# 4channelsRelay.net
KiCad netlist of a schematic drawn in EAGLE
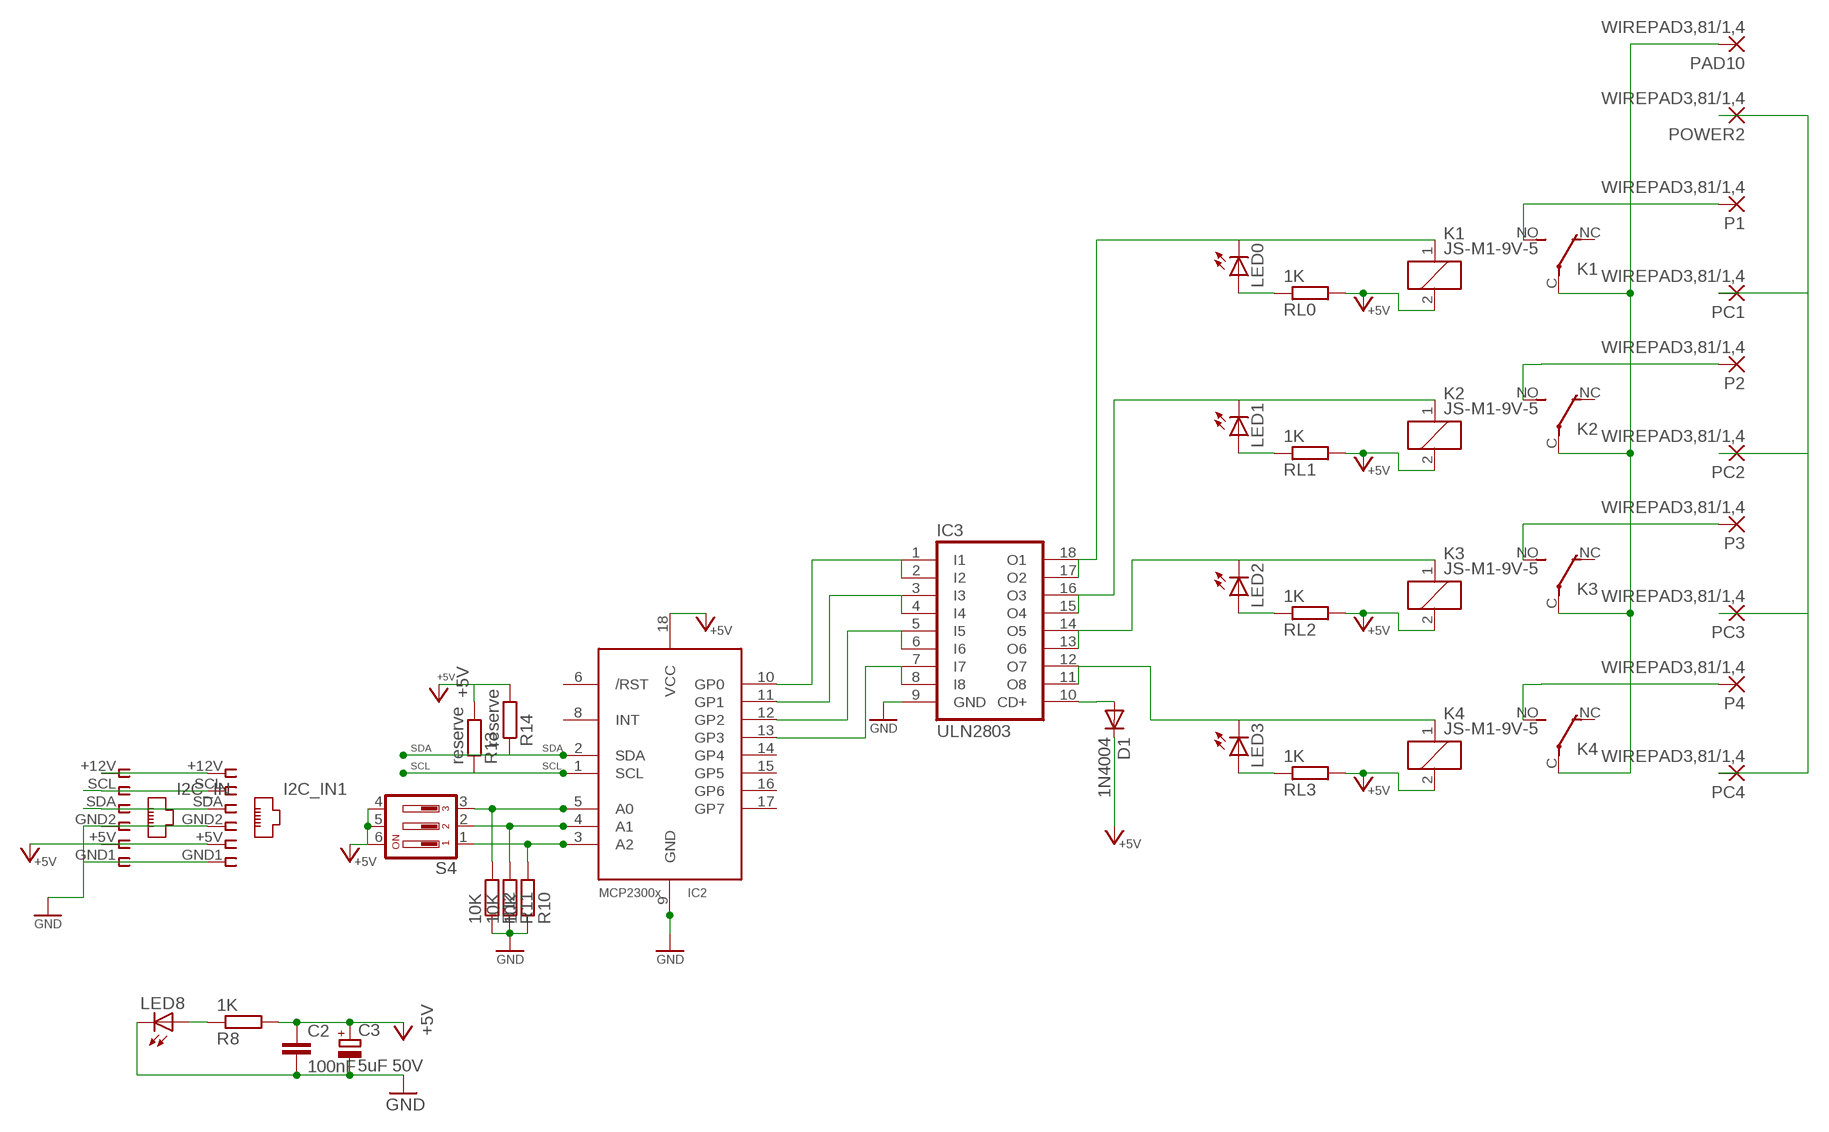
[diagram p0: schematic, sheet 1]

(export (version "E")
  (design (tool "Eeschema 10.0.6"))
  (components
    (comp (ref "C2")
      (value "100nF")
      (footprint "eagle-import:C1206")
      (libsource (lib "eagle-import") (part "C-EUC1206"))
    )
    (comp (ref "C3")
      (value "5uF 50V")
      (footprint "eagle-import:E3,5-8")
      (libsource (lib "eagle-import") (part "CPOL-EUE3.5-8"))
    )
    (comp (ref "D1")
      (value "1N4004")
      (footprint "eagle-import:DO41-10")
      (libsource (lib "eagle-import") (part "1N4004"))
    )
    (comp (ref "I2C_IN")
      (value "I2C 1")
      (footprint "eagle-import:RJ12-STRAIGHT-I2C")
      (libsource (lib "eagle-import") (part "RJ12STRAIGHT-I2C"))
    )
    (comp (ref "I2C_IN1")
      (value "I2C 2")
      (footprint "eagle-import:RJ12-STRAIGHT-I2C")
      (libsource (lib "eagle-import") (part "RJ12STRAIGHT-I2C"))
    )
    (comp (ref "IC2")
      (value "MCP2300X/P")
      (footprint "eagle-import:DIL18")
      (libsource (lib "eagle-import") (part "MCP2300X/P"))
    )
    (comp (ref "IC3")
      (value "ULN2803")
      (footprint "eagle-import:DIL18")
      (libsource (lib "eagle-import") (part "ULN2803A"))
    )
    (comp (ref "K1")
      (value "JS-M1-9V-5")
      (footprint "eagle-import:JS-M")
      (libsource (lib "eagle-import") (part "JS-M1-9V-5"))
    )
    (comp (ref "K2")
      (value "JS-M1-9V-5")
      (footprint "eagle-import:JS-M")
      (libsource (lib "eagle-import") (part "JS-M1-9V-5"))
    )
    (comp (ref "K3")
      (value "JS-M1-9V-5")
      (footprint "eagle-import:JS-M")
      (libsource (lib "eagle-import") (part "JS-M1-9V-5"))
    )
    (comp (ref "K4")
      (value "JS-M1-9V-5")
      (footprint "eagle-import:JS-M")
      (libsource (lib "eagle-import") (part "JS-M1-9V-5"))
    )
    (comp (ref "LED0")
      (value "LED3MM")
      (footprint "eagle-import:LED3MM")
      (libsource (lib "eagle-import") (part "LED3MM"))
    )
    (comp (ref "LED1")
      (value "LED3MM")
      (footprint "eagle-import:LED3MM")
      (libsource (lib "eagle-import") (part "LED3MM"))
    )
    (comp (ref "LED2")
      (value "LED3MM")
      (footprint "eagle-import:LED3MM")
      (libsource (lib "eagle-import") (part "LED3MM"))
    )
    (comp (ref "LED3")
      (value "LED3MM")
      (footprint "eagle-import:LED3MM")
      (libsource (lib "eagle-import") (part "LED3MM"))
    )
    (comp (ref "LED8")
      (value "LED3MM")
      (footprint "eagle-import:LED3MM")
      (libsource (lib "eagle-import") (part "LED3MM"))
    )
    (comp (ref "P1")
      (value "WIREPAD3,81/1,4")
      (footprint "eagle-import:3,81_1,4")
      (libsource (lib "eagle-import") (part "WIREPAD3,81/1,4"))
    )
    (comp (ref "P2")
      (value "WIREPAD3,81/1,4")
      (footprint "eagle-import:3,81_1,4")
      (libsource (lib "eagle-import") (part "WIREPAD3,81/1,4"))
    )
    (comp (ref "P3")
      (value "WIREPAD3,81/1,4")
      (footprint "eagle-import:3,81_1,4")
      (libsource (lib "eagle-import") (part "WIREPAD3,81/1,4"))
    )
    (comp (ref "P4")
      (value "WIREPAD3,81/1,4")
      (footprint "eagle-import:3,81_1,4")
      (libsource (lib "eagle-import") (part "WIREPAD3,81/1,4"))
    )
    (comp (ref "PAD10")
      (value "WIREPAD3,81/1,4")
      (footprint "eagle-import:3,81_1,4")
      (libsource (lib "eagle-import") (part "WIREPAD3,81/1,4"))
    )
    (comp (ref "PC1")
      (value "WIREPAD3,81/1,4")
      (footprint "eagle-import:3,81_1,4")
      (libsource (lib "eagle-import") (part "WIREPAD3,81/1,4"))
    )
    (comp (ref "PC2")
      (value "WIREPAD3,81/1,4")
      (footprint "eagle-import:3,81_1,4")
      (libsource (lib "eagle-import") (part "WIREPAD3,81/1,4"))
    )
    (comp (ref "PC3")
      (value "WIREPAD3,81/1,4")
      (footprint "eagle-import:3,81_1,4")
      (libsource (lib "eagle-import") (part "WIREPAD3,81/1,4"))
    )
    (comp (ref "PC4")
      (value "WIREPAD3,81/1,4")
      (footprint "eagle-import:3,81_1,4")
      (libsource (lib "eagle-import") (part "WIREPAD3,81/1,4"))
    )
    (comp (ref "POWER2")
      (value "WIREPAD3,81/1,4")
      (footprint "eagle-import:3,81_1,4")
      (libsource (lib "eagle-import") (part "WIREPAD3,81/1,4"))
    )
    (comp (ref "R8")
      (value "1K")
      (footprint "eagle-import:M1206")
      (libsource (lib "eagle-import") (part "R-EU_M1206"))
    )
    (comp (ref "R10")
      (value "10K")
      (footprint "eagle-import:M1206")
      (libsource (lib "eagle-import") (part "R-EU_M1206"))
    )
    (comp (ref "R11")
      (value "10K")
      (footprint "eagle-import:M1206")
      (libsource (lib "eagle-import") (part "R-EU_M1206"))
    )
    (comp (ref "R12")
      (value "10K")
      (footprint "eagle-import:M1206")
      (libsource (lib "eagle-import") (part "R-EU_M1206"))
    )
    (comp (ref "R13")
      (value "reserve")
      (footprint "eagle-import:M1206")
      (libsource (lib "eagle-import") (part "R-EU_M1206"))
    )
    (comp (ref "R14")
      (value "reserve")
      (footprint "eagle-import:M1206")
      (libsource (lib "eagle-import") (part "R-EU_M1206"))
    )
    (comp (ref "RL0")
      (value "1K")
      (footprint "eagle-import:M1206")
      (libsource (lib "eagle-import") (part "R-EU_M1206"))
    )
    (comp (ref "RL1")
      (value "1K")
      (footprint "eagle-import:M1206")
      (libsource (lib "eagle-import") (part "R-EU_M1206"))
    )
    (comp (ref "RL2")
      (value "1K")
      (footprint "eagle-import:M1206")
      (libsource (lib "eagle-import") (part "R-EU_M1206"))
    )
    (comp (ref "RL3")
      (value "1K")
      (footprint "eagle-import:M1206")
      (libsource (lib "eagle-import") (part "R-EU_M1206"))
    )
    (comp (ref "S4")
      (value "DIP03YL")
      (footprint "eagle-import:DIP03YL")
      (libsource (lib "eagle-import") (part "DIP03YL"))
    )
  )
  (nets
    (net (code "1") (name "+5V") (class "Default")
      (node (ref "C2") (pin "1") (pinfunction "1_1") (pintype "passive"))
      (node (ref "C3") (pin "+") (pinfunction "+_+") (pintype "passive"))
      (node (ref "D1") (pin "C") (pinfunction "C_C") (pintype "passive"))
      (node (ref "I2C_IN") (pin "+5V") (pinfunction "5_+5V") (pintype "power_in"))
      (node (ref "I2C_IN1") (pin "+5V") (pinfunction "5_+5V") (pintype "power_in"))
      (node (ref "IC2") (pin "18") (pinfunction "VCC_18") (pintype "power_in"))
      (node (ref "K1") (pin "2") (pinfunction "2_2") (pintype "passive"))
      (node (ref "K2") (pin "2") (pinfunction "2_2") (pintype "passive"))
      (node (ref "K3") (pin "2") (pinfunction "2_2") (pintype "passive"))
      (node (ref "K4") (pin "2") (pinfunction "2_2") (pintype "passive"))
      (node (ref "R13") (pin "2") (pinfunction "2_2") (pintype "passive"))
      (node (ref "R14") (pin "2") (pinfunction "2_2") (pintype "passive"))
      (node (ref "R8") (pin "2") (pinfunction "2_2") (pintype "passive"))
      (node (ref "RL0") (pin "2") (pinfunction "2_2") (pintype "passive"))
      (node (ref "RL1") (pin "2") (pinfunction "2_2") (pintype "passive"))
      (node (ref "RL2") (pin "2") (pinfunction "2_2") (pintype "passive"))
      (node (ref "RL3") (pin "2") (pinfunction "2_2") (pintype "passive"))
      (node (ref "S4") (pin "4") (pinfunction "4_4") (pintype "passive"))
      (node (ref "S4") (pin "5") (pinfunction "5_5") (pintype "passive"))
      (node (ref "S4") (pin "6") (pinfunction "6_6") (pintype "passive"))
    )
    (net (code "2") (name "/SCL") (class "Default")
      (node (ref "I2C_IN") (pin "SCL") (pinfunction "2_SCL") (pintype "bidirectional"))
      (node (ref "I2C_IN1") (pin "SCL") (pinfunction "2_SCL") (pintype "bidirectional"))
      (node (ref "IC2") (pin "1") (pinfunction "SCL_1") (pintype "bidirectional"))
      (node (ref "R13") (pin "1") (pinfunction "1_1") (pintype "passive"))
    )
    (net (code "3") (name "/SDA") (class "Default")
      (node (ref "I2C_IN") (pin "SDA") (pinfunction "3_SDA") (pintype "bidirectional"))
      (node (ref "I2C_IN1") (pin "SDA") (pinfunction "3_SDA") (pintype "bidirectional"))
      (node (ref "IC2") (pin "2") (pinfunction "SDA_2") (pintype "bidirectional"))
      (node (ref "R14") (pin "1") (pinfunction "1_1") (pintype "passive"))
    )
    (net (code "4") (name "GND") (class "Default")
      (node (ref "C2") (pin "2") (pinfunction "2_2") (pintype "passive"))
      (node (ref "C3") (pin "-") (pinfunction "-_-") (pintype "passive"))
      (node (ref "I2C_IN") (pin "GND1") (pinfunction "6_GND1") (pintype "power_in"))
      (node (ref "I2C_IN") (pin "GND2") (pinfunction "4_GND2") (pintype "power_in"))
      (node (ref "I2C_IN1") (pin "GND1") (pinfunction "6_GND1") (pintype "power_in"))
      (node (ref "I2C_IN1") (pin "GND2") (pinfunction "4_GND2") (pintype "power_in"))
      (node (ref "IC2") (pin "9") (pinfunction "GND_9") (pintype "power_in"))
      (node (ref "IC3") (pin "9") (pinfunction "GND_9") (pintype "power_in"))
      (node (ref "LED8") (pin "K") (pinfunction "C_K") (pintype "passive"))
      (node (ref "R10") (pin "1") (pinfunction "1_1") (pintype "passive"))
      (node (ref "R11") (pin "1") (pinfunction "1_1") (pintype "passive"))
      (node (ref "R12") (pin "1") (pinfunction "1_1") (pintype "passive"))
    )
    (net (code "5") (name "Net-(I2C_IN-1)") (class "Default")
      (node (ref "I2C_IN") (pin "+12V") (pinfunction "1_+12V") (pintype "power_in"))
      (node (ref "I2C_IN1") (pin "+12V") (pinfunction "1_+12V") (pintype "power_in"))
    )
    (net (code "6") (name "Net-(IC2-A0)") (class "Default")
      (node (ref "IC2") (pin "5") (pinfunction "A0_5") (pintype "input"))
      (node (ref "R12") (pin "2") (pinfunction "2_2") (pintype "passive"))
      (node (ref "S4") (pin "3") (pinfunction "3_3") (pintype "passive"))
    )
    (net (code "7") (name "Net-(IC2-A1)") (class "Default")
      (node (ref "IC2") (pin "4") (pinfunction "A1_4") (pintype "input"))
      (node (ref "R11") (pin "2") (pinfunction "2_2") (pintype "passive"))
      (node (ref "S4") (pin "2") (pinfunction "2_2") (pintype "passive"))
    )
    (net (code "8") (name "Net-(IC2-A2)") (class "Default")
      (node (ref "IC2") (pin "3") (pinfunction "A2_3") (pintype "input"))
      (node (ref "R10") (pin "2") (pinfunction "2_2") (pintype "passive"))
      (node (ref "S4") (pin "1") (pinfunction "1_1") (pintype "passive"))
    )
    (net (code "9") (name "Net-(IC2-GP0)") (class "Default")
      (node (ref "IC2") (pin "10") (pinfunction "GP0_10") (pintype "bidirectional"))
      (node (ref "IC3") (pin "1") (pinfunction "I1_1") (pintype "input"))
      (node (ref "IC3") (pin "2") (pinfunction "I2_2") (pintype "input"))
    )
    (net (code "10") (name "Net-(IC2-GP1)") (class "Default")
      (node (ref "IC2") (pin "11") (pinfunction "GP1_11") (pintype "bidirectional"))
      (node (ref "IC3") (pin "3") (pinfunction "I3_3") (pintype "input"))
      (node (ref "IC3") (pin "4") (pinfunction "I4_4") (pintype "input"))
    )
    (net (code "11") (name "Net-(IC2-GP2)") (class "Default")
      (node (ref "IC2") (pin "12") (pinfunction "GP2_12") (pintype "bidirectional"))
      (node (ref "IC3") (pin "5") (pinfunction "I5_5") (pintype "input"))
      (node (ref "IC3") (pin "6") (pinfunction "I6_6") (pintype "input"))
    )
    (net (code "12") (name "Net-(IC2-GP3)") (class "Default")
      (node (ref "IC2") (pin "13") (pinfunction "GP3_13") (pintype "bidirectional"))
      (node (ref "IC3") (pin "7") (pinfunction "I7_7") (pintype "input"))
      (node (ref "IC3") (pin "8") (pinfunction "I8_8") (pintype "input"))
    )
    (net (code "13") (name "Net-(IC3-CD+)") (class "Default")
      (node (ref "D1") (pin "A") (pinfunction "A_A") (pintype "passive"))
      (node (ref "IC3") (pin "10") (pinfunction "CD+_10") (pintype "passive"))
    )
    (net (code "14") (name "Net-(IC3-O1)") (class "Default")
      (node (ref "IC3") (pin "17") (pinfunction "O2_17") (pintype "open_collector"))
      (node (ref "IC3") (pin "18") (pinfunction "O1_18") (pintype "open_collector"))
      (node (ref "K1") (pin "1") (pinfunction "1_1") (pintype "passive"))
      (node (ref "LED0") (pin "K") (pinfunction "C_K") (pintype "passive"))
    )
    (net (code "15") (name "Net-(IC3-O3)") (class "Default")
      (node (ref "IC3") (pin "15") (pinfunction "O4_15") (pintype "open_collector"))
      (node (ref "IC3") (pin "16") (pinfunction "O3_16") (pintype "open_collector"))
      (node (ref "K2") (pin "1") (pinfunction "1_1") (pintype "passive"))
      (node (ref "LED1") (pin "K") (pinfunction "C_K") (pintype "passive"))
    )
    (net (code "16") (name "Net-(IC3-O5)") (class "Default")
      (node (ref "IC3") (pin "13") (pinfunction "O6_13") (pintype "open_collector"))
      (node (ref "IC3") (pin "14") (pinfunction "O5_14") (pintype "open_collector"))
      (node (ref "K3") (pin "1") (pinfunction "1_1") (pintype "passive"))
      (node (ref "LED2") (pin "K") (pinfunction "C_K") (pintype "passive"))
    )
    (net (code "17") (name "Net-(IC3-O7)") (class "Default")
      (node (ref "IC3") (pin "11") (pinfunction "O8_11") (pintype "open_collector"))
      (node (ref "IC3") (pin "12") (pinfunction "O7_12") (pintype "open_collector"))
      (node (ref "K4") (pin "1") (pinfunction "1_1") (pintype "passive"))
      (node (ref "LED3") (pin "K") (pinfunction "C_K") (pintype "passive"))
    )
    (net (code "18") (name "Net-(K1B-P)") (class "Default")
      (node (ref "K1") (pin "C") (pinfunction "P_C") (pintype "passive"))
      (node (ref "K2") (pin "C") (pinfunction "P_C") (pintype "passive"))
      (node (ref "K3") (pin "C") (pinfunction "P_C") (pintype "passive"))
      (node (ref "K4") (pin "C") (pinfunction "P_C") (pintype "passive"))
      (node (ref "PAD10") (pin "1") (pinfunction "P_1") (pintype "passive"))
    )
    (net (code "19") (name "Net-(K1B-S)") (class "Default")
      (node (ref "K1") (pin "NO") (pinfunction "S_NO") (pintype "passive"))
      (node (ref "P1") (pin "1") (pinfunction "P_1") (pintype "passive"))
    )
    (net (code "20") (name "Net-(K2B-S)") (class "Default")
      (node (ref "K2") (pin "NO") (pinfunction "S_NO") (pintype "passive"))
      (node (ref "P2") (pin "1") (pinfunction "P_1") (pintype "passive"))
    )
    (net (code "21") (name "Net-(K3B-S)") (class "Default")
      (node (ref "K3") (pin "NO") (pinfunction "S_NO") (pintype "passive"))
      (node (ref "P3") (pin "1") (pinfunction "P_1") (pintype "passive"))
    )
    (net (code "22") (name "Net-(K4B-S)") (class "Default")
      (node (ref "K4") (pin "NO") (pinfunction "S_NO") (pintype "passive"))
      (node (ref "P4") (pin "1") (pinfunction "P_1") (pintype "passive"))
    )
    (net (code "23") (name "Net-(LED0-PadA)") (class "Default")
      (node (ref "LED0") (pin "A") (pinfunction "A_A") (pintype "passive"))
      (node (ref "RL0") (pin "1") (pinfunction "1_1") (pintype "passive"))
    )
    (net (code "24") (name "Net-(LED1-PadA)") (class "Default")
      (node (ref "LED1") (pin "A") (pinfunction "A_A") (pintype "passive"))
      (node (ref "RL1") (pin "1") (pinfunction "1_1") (pintype "passive"))
    )
    (net (code "25") (name "Net-(LED2-PadA)") (class "Default")
      (node (ref "LED2") (pin "A") (pinfunction "A_A") (pintype "passive"))
      (node (ref "RL2") (pin "1") (pinfunction "1_1") (pintype "passive"))
    )
    (net (code "26") (name "Net-(LED3-PadA)") (class "Default")
      (node (ref "LED3") (pin "A") (pinfunction "A_A") (pintype "passive"))
      (node (ref "RL3") (pin "1") (pinfunction "1_1") (pintype "passive"))
    )
    (net (code "27") (name "Net-(LED8-PadA)") (class "Default")
      (node (ref "LED8") (pin "A") (pinfunction "A_A") (pintype "passive"))
      (node (ref "R8") (pin "1") (pinfunction "1_1") (pintype "passive"))
    )
    (net (code "28") (name "Net-(PC1-P)") (class "Default")
      (node (ref "PC1") (pin "1") (pinfunction "P_1") (pintype "passive"))
      (node (ref "PC2") (pin "1") (pinfunction "P_1") (pintype "passive"))
      (node (ref "PC3") (pin "1") (pinfunction "P_1") (pintype "passive"))
      (node (ref "PC4") (pin "1") (pinfunction "P_1") (pintype "passive"))
      (node (ref "POWER2") (pin "1") (pinfunction "P_1") (pintype "passive"))
    )
    (net (code "29") (name "unconnected-(IC2-GP4-Pad14)") (class "Default")
      (node (ref "IC2") (pin "14") (pinfunction "GP4_14") (pintype "bidirectional"))
    )
    (net (code "30") (name "unconnected-(IC2-GP5-Pad15)") (class "Default")
      (node (ref "IC2") (pin "15") (pinfunction "GP5_15") (pintype "bidirectional"))
    )
    (net (code "31") (name "unconnected-(IC2-GP6-Pad16)") (class "Default")
      (node (ref "IC2") (pin "16") (pinfunction "GP6_16") (pintype "bidirectional"))
    )
    (net (code "32") (name "unconnected-(IC2-GP7-Pad17)") (class "Default")
      (node (ref "IC2") (pin "17") (pinfunction "GP7_17") (pintype "bidirectional"))
    )
    (net (code "33") (name "unconnected-(IC2-INT-Pad8)") (class "Default")
      (node (ref "IC2") (pin "8") (pinfunction "INT_8") (pintype "output"))
    )
    (net (code "34") (name "unconnected-(IC2-{slash}RST-Pad6)") (class "Default")
      (node (ref "IC2") (pin "6") (pinfunction "/RST_6") (pintype "input"))
    )
    (net (code "35") (name "unconnected-(K1B-O-PadNC)") (class "Default")
      (node (ref "K1") (pin "NC") (pinfunction "O_NC") (pintype "passive"))
    )
    (net (code "36") (name "unconnected-(K2B-O-PadNC)") (class "Default")
      (node (ref "K2") (pin "NC") (pinfunction "O_NC") (pintype "passive"))
    )
    (net (code "37") (name "unconnected-(K3B-O-PadNC)") (class "Default")
      (node (ref "K3") (pin "NC") (pinfunction "O_NC") (pintype "passive"))
    )
    (net (code "38") (name "unconnected-(K4B-O-PadNC)") (class "Default")
      (node (ref "K4") (pin "NC") (pinfunction "O_NC") (pintype "passive"))
    )
  )
)
